# DRV8825_stepper_motor_controller.net
KiCad netlist of a schematic drawn in Altium Designer
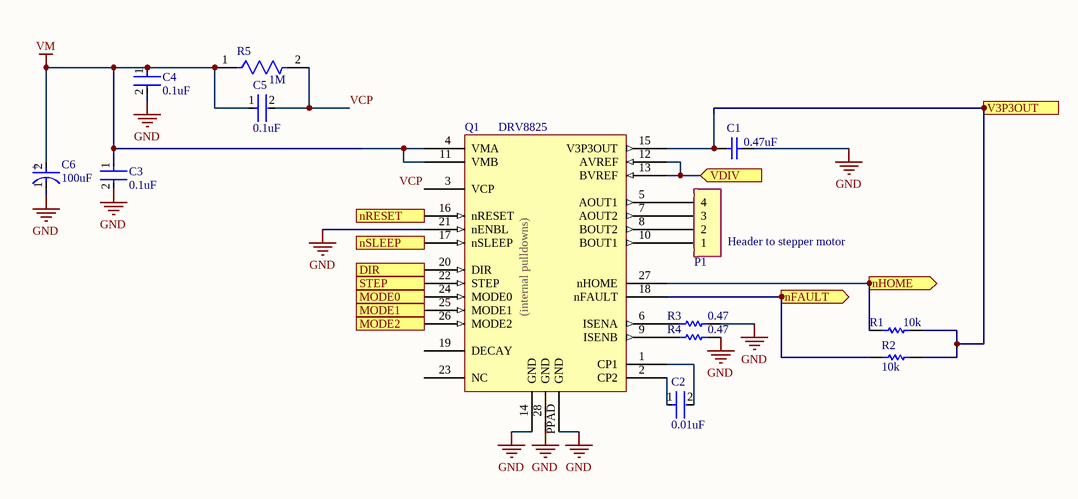
[diagram p0: DRV8825 stepper motor controller.SchDoc]

(export (version "E")
  (design (tool "Eeschema 10.0.6"))
  (components
    (comp (ref "C1")
      (value "0.47uF")
      (footprint "CAPC2013X140X50ML20T25")
      (fields (field (name "PART NUMBER") "C0805F474K3RACTU") (field (name "MANUFACTURER") "Kemet"))
      (libsource (lib "Altium Content Vault") (part "CAP"))
    )
    (comp (ref "C2")
      (value "0.01uF")
      (footprint "FP-0805-L_2_01_0_2-W_1_25-IPC_B")
      (description "General Purpose Ceramic Capacitor, 0805, 10nF, 5%, X7R, 0.15, 50V")
      (fields (field (name "VOLTAGE") "50V") (field (name "TOLERANCE") "5%"))
      (libsource (lib "Altium Content Vault") (part "02cd4be3c70576c341d710602a673aa"))
    )
    (comp (ref "C3")
      (value "0.1uF")
      (footprint "FP-0805-L_2_01_0_2-W_1_25-IPC_C")
      (description "General Purpose Ceramic Capacitor, 0805, 100nF, 10%, X7R, 0.15, 50V")
      (fields (field (name "TOLERANCE") "10%") (field (name "VOLTAGE") "50V"))
      (libsource (lib "Altium Content Vault") (part "02cd4be3c70576c341d710602a673aa"))
    )
    (comp (ref "C4")
      (value "0.1uF")
      (footprint "FP-0805-L_2_01_0_2-W_1_25-IPC_C")
      (description "General Purpose Ceramic Capacitor, 0805, 100nF, 10%, X7R, 0.15, 50V")
      (fields (field (name "TOLERANCE") "10%") (field (name "VOLTAGE") "50V"))
      (libsource (lib "Altium Content Vault") (part "02cd4be3c70576c341d710602a673aa"))
    )
    (comp (ref "C5")
      (value "0.1uF")
      (footprint "FP-0805-L_2_01_0_2-W_1_25-IPC_C")
      (description "General Purpose Ceramic Capacitor, 0805, 100nF, 10%, X7R, 0.15, 50V")
      (fields (field (name "TOLERANCE") "10%") (field (name "VOLTAGE") "50V"))
      (libsource (lib "Altium Content Vault") (part "02cd4be3c70576c341d710602a673aa"))
    )
    (comp (ref "C6")
      (value "100uF")
      (footprint "FP-FKE-MFG")
      (description "CAP ALUM 100UF 20% 25V SMD")
      (fields (field (name "TOLERANCE") "20%") (field (name "VOLTAGE") "25V"))
      (libsource (lib "Altium Content Vault") (part "203bc49f2ac43e59fd269a8c329ed05"))
    )
    (comp (ref "P1")
      (value "Header to stepper motor")
      (footprint "B4B-XH-A (LF)(SN)")
      (description "Wire-to-board connector, vertical, 2.5mm, 4 contacts")
      (libsource (lib "JCULibrary_AS2_v2") (part "B4B-XH-A (LF)(SN) Wire-to-board connector"))
    )
    (comp (ref "Q1")
      (value "DRV8825")
      (footprint "DRV8825 HTSSOP")
      (description "TI DRV8825 Stepper Motor Controller IC")
      (libsource (lib "JCULibrary_AS2_v2") (part "Stepper motor driver DRV8825"))
    )
    (comp (ref "R1")
      (value "10k")
      (footprint "RESC2013X60X35ML10T20")
      (description "Chip Resistor, 10 KOhm, +/- 5%, 0.125 W, -55 to 155 degC, 0805 (2012 Metric), RoHS, Tape and Reel")
      (fields (field (name "MANUFACTURER") "Yageo"))
      (libsource (lib "Altium Content Vault") (part "RES-2"))
    )
    (comp (ref "R2")
      (value "10k")
      (footprint "RESC2013X60X35ML10T20")
      (description "Chip Resistor, 10 KOhm, +/- 5%, 0.125 W, -55 to 155 degC, 0805 (2012 Metric), RoHS, Tape and Reel")
      (fields (field (name "MANUFACTURER") "Yageo"))
      (libsource (lib "Altium Content Vault") (part "RES-2"))
    )
    (comp (ref "R3")
      (value "0.47")
      (footprint "RESC2013X65X40ML15T20")
      (fields (field (name "PART NUMBER") "RCWE0805R470FKEA") (field (name "MANUFACTURER") "Vishay Dale"))
      (libsource (lib "Altium Content Vault") (part "RES"))
    )
    (comp (ref "R4")
      (value "0.47")
      (footprint "RESC2013X65X40ML15T20")
      (fields (field (name "PART NUMBER") "RCWE0805R470FKEA") (field (name "MANUFACTURER") "Vishay Dale"))
      (libsource (lib "Altium Content Vault") (part "RES"))
    )
    (comp (ref "R5")
      (value "1M")
      (footprint "FP-CRCW0805-e3-IPC_B")
      (description "RES Thick Film, 1MΩ, 1%, 0.125W, 100ppm/°C, 0805")
      (fields (field (name "TOLERANCE") "1%"))
      (libsource (lib "Altium Content Vault") (part "1029c3af85768c4190bb7ad29bc67b5"))
    )
  )
  (nets
    (net (code "1") (name "/DIR") (class "Default")
      (node (ref "Q1") (pin "20") (pinfunction "DIR_20") (pintype "input"))
    )
    (net (code "2") (name "/MODE0") (class "Default")
      (node (ref "Q1") (pin "24") (pinfunction "MODE0_24") (pintype "input"))
    )
    (net (code "3") (name "/MODE1") (class "Default")
      (node (ref "Q1") (pin "25") (pinfunction "MODE1_25") (pintype "input"))
    )
    (net (code "4") (name "/MODE2") (class "Default")
      (node (ref "Q1") (pin "26") (pinfunction "MODE2_26") (pintype "input"))
    )
    (net (code "5") (name "/STEP") (class "Default")
      (node (ref "Q1") (pin "22") (pinfunction "STEP_22") (pintype "input"))
    )
    (net (code "6") (name "/V3P3OUT") (class "Default")
      (node (ref "C1") (pin "1") (pinfunction "1_1") (pintype "passive"))
      (node (ref "Q1") (pin "15") (pinfunction "V3P3OUT_15") (pintype "output"))
      (node (ref "R1") (pin "2") (pinfunction "2_2") (pintype "passive"))
      (node (ref "R2") (pin "1") (pinfunction "1_1") (pintype "passive"))
    )
    (net (code "7") (name "/VCP") (class "Default")
      (node (ref "C5") (pin "2") (pinfunction "2_2") (pintype "passive"))
      (node (ref "Q1") (pin "3") (pinfunction "VCP_3") (pintype "power_in"))
      (node (ref "R5") (pin "2") (pinfunction "2_2") (pintype "passive"))
    )
    (net (code "8") (name "/VDIV") (class "Default")
      (node (ref "Q1") (pin "12") (pinfunction "AVREF_12") (pintype "input"))
      (node (ref "Q1") (pin "13") (pinfunction "BVREF_13") (pintype "input"))
    )
    (net (code "9") (name "/nFAULT") (class "Default")
      (node (ref "Q1") (pin "18") (pinfunction "nFAULT_18") (pintype "open_collector"))
      (node (ref "R2") (pin "2") (pinfunction "2_2") (pintype "passive"))
    )
    (net (code "10") (name "/nHOME") (class "Default")
      (node (ref "Q1") (pin "27") (pinfunction "nHOME_27") (pintype "open_collector"))
      (node (ref "R1") (pin "1") (pinfunction "1_1") (pintype "passive"))
    )
    (net (code "11") (name "/nRESET") (class "Default")
      (node (ref "Q1") (pin "16") (pinfunction "nRESET_16") (pintype "input"))
    )
    (net (code "12") (name "/nSLEEP") (class "Default")
      (node (ref "Q1") (pin "17") (pinfunction "nSLEEP_17") (pintype "input"))
    )
    (net (code "13") (name "GND") (class "Default")
      (node (ref "C1") (pin "2") (pinfunction "2_2") (pintype "passive"))
      (node (ref "C3") (pin "2") (pinfunction "2_2") (pintype "passive"))
      (node (ref "C4") (pin "2") (pinfunction "2_2") (pintype "passive"))
      (node (ref "C6") (pin "1") (pinfunction "C_1") (pintype "passive"))
      (node (ref "Q1") (pin "14") (pinfunction "GND_14") (pintype "power_in"))
      (node (ref "Q1") (pin "21") (pinfunction "nENBL_21") (pintype "input"))
      (node (ref "Q1") (pin "28") (pinfunction "GND_28") (pintype "power_in"))
      (node (ref "Q1") (pin "PPAD") (pinfunction "GND_PPAD") (pintype "power_in"))
      (node (ref "R3") (pin "2") (pinfunction "2_2") (pintype "passive"))
      (node (ref "R4") (pin "2") (pinfunction "2_2") (pintype "passive"))
    )
    (net (code "14") (name "Net-(Q1-AOUT1)") (class "Default")
      (node (ref "P1") (pin "4") (pinfunction "4_4") (pintype "passive"))
      (node (ref "Q1") (pin "5") (pinfunction "AOUT1_5") (pintype "output"))
    )
    (net (code "15") (name "Net-(Q1-AOUT2)") (class "Default")
      (node (ref "P1") (pin "3") (pinfunction "3_3") (pintype "passive"))
      (node (ref "Q1") (pin "7") (pinfunction "AOUT2_7") (pintype "output"))
    )
    (net (code "16") (name "Net-(Q1-BOUT1)") (class "Default")
      (node (ref "P1") (pin "1") (pinfunction "1_1") (pintype "passive"))
      (node (ref "Q1") (pin "10") (pinfunction "BOUT1_10") (pintype "output"))
    )
    (net (code "17") (name "Net-(Q1-BOUT2)") (class "Default")
      (node (ref "P1") (pin "2") (pinfunction "2_2") (pintype "passive"))
      (node (ref "Q1") (pin "8") (pinfunction "BOUT2_8") (pintype "output"))
    )
    (net (code "18") (name "Net-(Q1-CP1)") (class "Default")
      (node (ref "C2") (pin "2") (pinfunction "2_2") (pintype "passive"))
      (node (ref "Q1") (pin "1") (pinfunction "CP1_1") (pintype "power_in"))
    )
    (net (code "19") (name "Net-(Q1-CP2)") (class "Default")
      (node (ref "C2") (pin "1") (pinfunction "1_1") (pintype "passive"))
      (node (ref "Q1") (pin "2") (pinfunction "CP2_2") (pintype "power_in"))
    )
    (net (code "20") (name "Net-(Q1-ISENA)") (class "Default")
      (node (ref "Q1") (pin "6") (pinfunction "ISENA_6") (pintype "output"))
      (node (ref "R3") (pin "1") (pinfunction "1_1") (pintype "passive"))
    )
    (net (code "21") (name "Net-(Q1-ISENB)") (class "Default")
      (node (ref "Q1") (pin "9") (pinfunction "ISENB_9") (pintype "output"))
      (node (ref "R4") (pin "1") (pinfunction "1_1") (pintype "passive"))
    )
    (net (code "22") (name "VM") (class "Default")
      (node (ref "C3") (pin "1") (pinfunction "1_1") (pintype "passive"))
      (node (ref "C4") (pin "1") (pinfunction "1_1") (pintype "passive"))
      (node (ref "C5") (pin "1") (pinfunction "1_1") (pintype "passive"))
      (node (ref "C6") (pin "2") (pinfunction "A_2") (pintype "passive"))
      (node (ref "Q1") (pin "11") (pinfunction "VMB_11") (pintype "power_in"))
      (node (ref "Q1") (pin "4") (pinfunction "VMA_4") (pintype "power_in"))
      (node (ref "R5") (pin "1") (pinfunction "1_1") (pintype "passive"))
    )
    (net (code "23") (name "unconnected-(Q1-DECAY-Pad19)") (class "Default")
      (node (ref "Q1") (pin "19") (pinfunction "DECAY_19") (pintype "passive"))
    )
    (net (code "24") (name "unconnected-(Q1-NC-Pad23)") (class "Default")
      (node (ref "Q1") (pin "23") (pinfunction "NC_23") (pintype "passive"))
    )
  )
)
